# temp_controler_full.net
KiCad netlist of a schematic drawn in EAGLE
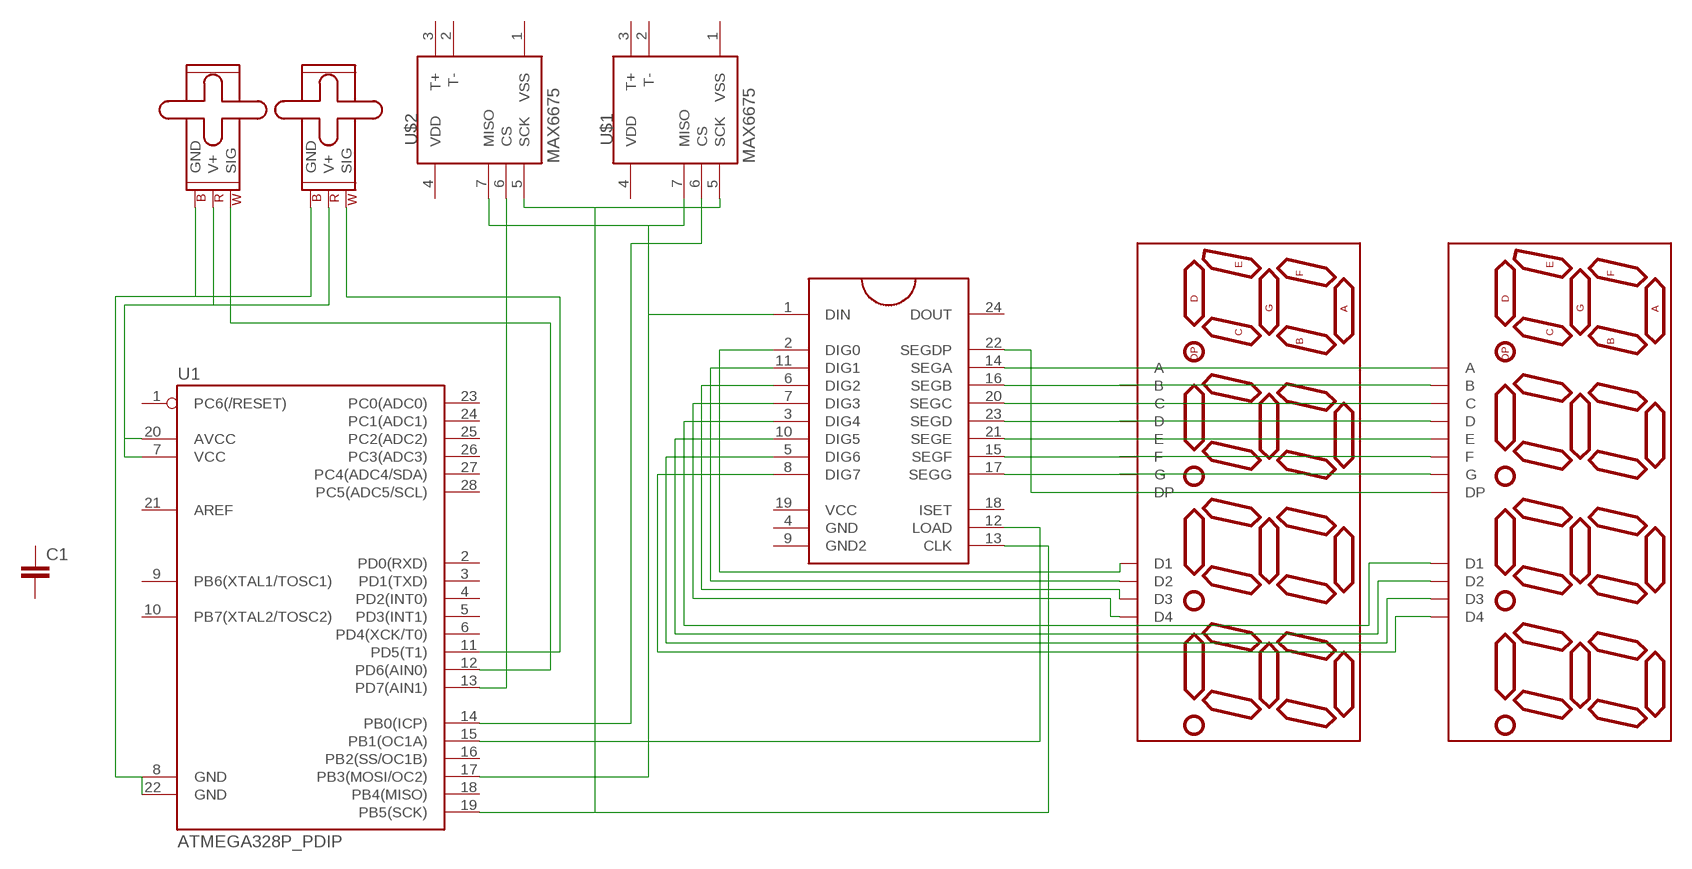
[diagram p0: schematic, sheet 1]

(export (version "E")
  (design (tool "Eeschema 10.0.6"))
  (components
    (comp (ref "C1")
      (value "0.1UF-50V-20%(PTH)KIT-EZ")
      (footprint "eagle-import:CAP-PTH-SMALL-KIT")
      (libsource (lib "eagle-import") (part "0.1UF-50V-20%(PTH)KIT-EZ"))
    )
    (comp (ref "M1")
      (value "SMALL_SERVO")
      (footprint "eagle-import:1X03")
      (libsource (lib "eagle-import") (part "SMALL_SERVO"))
    )
    (comp (ref "M2")
      (value "SMALL_SERVO")
      (footprint "eagle-import:1X03")
      (libsource (lib "eagle-import") (part "SMALL_SERVO"))
    )
    (comp (ref "U$1")
      (value "MAX6675")
      (footprint "eagle-import:SO08-MAX6675")
      (libsource (lib "eagle-import") (part "MAX6675"))
    )
    (comp (ref "U$2")
      (value "MAX6675")
      (footprint "eagle-import:SO08-MAX6675")
      (libsource (lib "eagle-import") (part "MAX6675"))
    )
    (comp (ref "U$3")
      (value "MAX7219DIP")
      (footprint "eagle-import:DIL24")
      (libsource (lib "eagle-import") (part "MAX7219DIP"))
    )
    (comp (ref "U$4")
      (value "7-SEGMENT-4DIGIT-COUNTERPTH")
      (footprint "eagle-import:7-SEGMENT-4DIGIT-COUNTER")
      (libsource (lib "eagle-import") (part "7-SEGMENT-4DIGIT-COUNTERPTH"))
    )
    (comp (ref "U$5")
      (value "7-SEGMENT-4DIGIT-COUNTERPTH")
      (footprint "eagle-import:7-SEGMENT-4DIGIT-COUNTER")
      (libsource (lib "eagle-import") (part "7-SEGMENT-4DIGIT-COUNTERPTH"))
    )
    (comp (ref "U1")
      (value "ATMEGA328P_PDIP")
      (footprint "eagle-import:DIL28-3")
      (libsource (lib "eagle-import") (part "ATMEGA328P_PDIP"))
    )
  )
  (nets
    (net (code "1") (name "Net-(M1-GND)") (class "Default")
      (node (ref "M1") (pin "3") (pinfunction "GND_3") (pintype "bidirectional"))
      (node (ref "M2") (pin "3") (pinfunction "GND_3") (pintype "bidirectional"))
      (node (ref "U1") (pin "22") (pinfunction "GND_22") (pintype "bidirectional"))
      (node (ref "U1") (pin "8") (pinfunction "GND_8") (pintype "bidirectional"))
    )
    (net (code "2") (name "Net-(M1-SIG)") (class "Default")
      (node (ref "M1") (pin "1") (pinfunction "SIG_1") (pintype "bidirectional"))
      (node (ref "U1") (pin "12") (pinfunction "PD6(AIN0)_12") (pintype "bidirectional"))
    )
    (net (code "3") (name "Net-(M1-V+)") (class "Default")
      (node (ref "M1") (pin "2") (pinfunction "V+_2") (pintype "bidirectional"))
      (node (ref "M2") (pin "2") (pinfunction "V+_2") (pintype "bidirectional"))
      (node (ref "U1") (pin "20") (pinfunction "AVCC_20") (pintype "bidirectional"))
      (node (ref "U1") (pin "7") (pinfunction "VCC_7") (pintype "bidirectional"))
    )
    (net (code "4") (name "Net-(M2-SIG)") (class "Default")
      (node (ref "M2") (pin "1") (pinfunction "SIG_1") (pintype "bidirectional"))
      (node (ref "U1") (pin "11") (pinfunction "PD5(T1)_11") (pintype "bidirectional"))
    )
    (net (code "5") (name "Net-(U$1-CS)") (class "Default")
      (node (ref "U$1") (pin "6") (pinfunction "CS_6") (pintype "bidirectional"))
      (node (ref "U1") (pin "14") (pinfunction "PB0(ICP)_14") (pintype "bidirectional"))
    )
    (net (code "6") (name "Net-(U$1-MISO)") (class "Default")
      (node (ref "U$1") (pin "7") (pinfunction "MISO_7") (pintype "bidirectional"))
      (node (ref "U$2") (pin "7") (pinfunction "MISO_7") (pintype "bidirectional"))
      (node (ref "U$3") (pin "1") (pinfunction "DIN_1") (pintype "bidirectional"))
      (node (ref "U1") (pin "17") (pinfunction "PB3(MOSI/OC2)_17") (pintype "bidirectional"))
    )
    (net (code "7") (name "Net-(U$1-SCK)") (class "Default")
      (node (ref "U$1") (pin "5") (pinfunction "SCK_5") (pintype "bidirectional"))
      (node (ref "U$2") (pin "5") (pinfunction "SCK_5") (pintype "bidirectional"))
      (node (ref "U$3") (pin "13") (pinfunction "CLK_13") (pintype "bidirectional"))
      (node (ref "U1") (pin "19") (pinfunction "PB5(SCK)_19") (pintype "bidirectional"))
    )
    (net (code "8") (name "Net-(U$2-CS)") (class "Default")
      (node (ref "U$2") (pin "6") (pinfunction "CS_6") (pintype "bidirectional"))
      (node (ref "U1") (pin "13") (pinfunction "PD7(AIN1)_13") (pintype "bidirectional"))
    )
    (net (code "9") (name "Net-(U$3-DIG0)") (class "Default")
      (node (ref "U$3") (pin "2") (pinfunction "DIG0_2") (pintype "bidirectional"))
      (node (ref "U$4") (pin "12") (pinfunction "D1_12") (pintype "bidirectional"))
    )
    (net (code "10") (name "Net-(U$3-DIG1)") (class "Default")
      (node (ref "U$3") (pin "11") (pinfunction "DIG1_11") (pintype "bidirectional"))
      (node (ref "U$4") (pin "9") (pinfunction "D2_9") (pintype "bidirectional"))
    )
    (net (code "11") (name "Net-(U$3-DIG2)") (class "Default")
      (node (ref "U$3") (pin "6") (pinfunction "DIG2_6") (pintype "bidirectional"))
      (node (ref "U$4") (pin "8") (pinfunction "D3_8") (pintype "bidirectional"))
    )
    (net (code "12") (name "Net-(U$3-DIG3)") (class "Default")
      (node (ref "U$3") (pin "7") (pinfunction "DIG3_7") (pintype "bidirectional"))
      (node (ref "U$4") (pin "6") (pinfunction "D4_6") (pintype "bidirectional"))
    )
    (net (code "13") (name "Net-(U$3-DIG4)") (class "Default")
      (node (ref "U$3") (pin "3") (pinfunction "DIG4_3") (pintype "bidirectional"))
      (node (ref "U$5") (pin "12") (pinfunction "D1_12") (pintype "bidirectional"))
    )
    (net (code "14") (name "Net-(U$3-DIG5)") (class "Default")
      (node (ref "U$3") (pin "10") (pinfunction "DIG5_10") (pintype "bidirectional"))
      (node (ref "U$5") (pin "9") (pinfunction "D2_9") (pintype "bidirectional"))
    )
    (net (code "15") (name "Net-(U$3-DIG6)") (class "Default")
      (node (ref "U$3") (pin "5") (pinfunction "DIG6_5") (pintype "bidirectional"))
      (node (ref "U$5") (pin "8") (pinfunction "D3_8") (pintype "bidirectional"))
    )
    (net (code "16") (name "Net-(U$3-DIG7)") (class "Default")
      (node (ref "U$3") (pin "8") (pinfunction "DIG7_8") (pintype "bidirectional"))
      (node (ref "U$5") (pin "6") (pinfunction "D4_6") (pintype "bidirectional"))
    )
    (net (code "17") (name "Net-(U$3-LOAD)") (class "Default")
      (node (ref "U$3") (pin "12") (pinfunction "LOAD_12") (pintype "bidirectional"))
      (node (ref "U1") (pin "15") (pinfunction "PB1(OC1A)_15") (pintype "bidirectional"))
    )
    (net (code "18") (name "Net-(U$3-SEGA)") (class "Default")
      (node (ref "U$3") (pin "14") (pinfunction "SEGA_14") (pintype "bidirectional"))
      (node (ref "U$4") (pin "11") (pinfunction "A_11") (pintype "bidirectional"))
      (node (ref "U$5") (pin "11") (pinfunction "A_11") (pintype "bidirectional"))
    )
    (net (code "19") (name "Net-(U$3-SEGB)") (class "Default")
      (node (ref "U$3") (pin "16") (pinfunction "SEGB_16") (pintype "bidirectional"))
      (node (ref "U$4") (pin "7") (pinfunction "B_7") (pintype "bidirectional"))
      (node (ref "U$5") (pin "7") (pinfunction "B_7") (pintype "bidirectional"))
    )
    (net (code "20") (name "Net-(U$3-SEGC)") (class "Default")
      (node (ref "U$3") (pin "20") (pinfunction "SEGC_20") (pintype "bidirectional"))
      (node (ref "U$4") (pin "4") (pinfunction "C_4") (pintype "bidirectional"))
      (node (ref "U$5") (pin "4") (pinfunction "C_4") (pintype "bidirectional"))
    )
    (net (code "21") (name "Net-(U$3-SEGD)") (class "Default")
      (node (ref "U$3") (pin "23") (pinfunction "SEGD_23") (pintype "bidirectional"))
      (node (ref "U$4") (pin "2") (pinfunction "D_2") (pintype "bidirectional"))
      (node (ref "U$5") (pin "2") (pinfunction "D_2") (pintype "bidirectional"))
    )
    (net (code "22") (name "Net-(U$3-SEGDP)") (class "Default")
      (node (ref "U$3") (pin "22") (pinfunction "SEGDP_22") (pintype "bidirectional"))
      (node (ref "U$4") (pin "3") (pinfunction "DP_3") (pintype "bidirectional"))
      (node (ref "U$5") (pin "3") (pinfunction "DP_3") (pintype "bidirectional"))
    )
    (net (code "23") (name "Net-(U$3-SEGE)") (class "Default")
      (node (ref "U$3") (pin "21") (pinfunction "SEGE_21") (pintype "bidirectional"))
      (node (ref "U$4") (pin "1") (pinfunction "E_1") (pintype "bidirectional"))
      (node (ref "U$5") (pin "1") (pinfunction "E_1") (pintype "bidirectional"))
    )
    (net (code "24") (name "Net-(U$3-SEGF)") (class "Default")
      (node (ref "U$3") (pin "15") (pinfunction "SEGF_15") (pintype "bidirectional"))
      (node (ref "U$4") (pin "10") (pinfunction "F_10") (pintype "bidirectional"))
      (node (ref "U$5") (pin "10") (pinfunction "F_10") (pintype "bidirectional"))
    )
    (net (code "25") (name "Net-(U$3-SEGG)") (class "Default")
      (node (ref "U$3") (pin "17") (pinfunction "SEGG_17") (pintype "bidirectional"))
      (node (ref "U$4") (pin "5") (pinfunction "G_5") (pintype "bidirectional"))
      (node (ref "U$5") (pin "5") (pinfunction "G_5") (pintype "bidirectional"))
    )
    (net (code "26") (name "unconnected-(C1-Pad1)") (class "Default")
      (node (ref "C1") (pin "1") (pinfunction "1_1") (pintype "passive"))
    )
    (net (code "27") (name "unconnected-(C1-Pad2)") (class "Default")
      (node (ref "C1") (pin "2") (pinfunction "2_2") (pintype "passive"))
    )
    (net (code "28") (name "unconnected-(U$1-T+-Pad3)") (class "Default")
      (node (ref "U$1") (pin "3") (pinfunction "T+_3") (pintype "bidirectional"))
    )
    (net (code "29") (name "unconnected-(U$1-T--Pad2)") (class "Default")
      (node (ref "U$1") (pin "2") (pinfunction "T-_2") (pintype "bidirectional"))
    )
    (net (code "30") (name "unconnected-(U$1-VDD-Pad4)") (class "Default")
      (node (ref "U$1") (pin "4") (pinfunction "VDD_4") (pintype "bidirectional"))
    )
    (net (code "31") (name "unconnected-(U$1-VSS-Pad1)") (class "Default")
      (node (ref "U$1") (pin "1") (pinfunction "VSS_1") (pintype "bidirectional"))
    )
    (net (code "32") (name "unconnected-(U$2-T+-Pad3)") (class "Default")
      (node (ref "U$2") (pin "3") (pinfunction "T+_3") (pintype "bidirectional"))
    )
    (net (code "33") (name "unconnected-(U$2-T--Pad2)") (class "Default")
      (node (ref "U$2") (pin "2") (pinfunction "T-_2") (pintype "bidirectional"))
    )
    (net (code "34") (name "unconnected-(U$2-VDD-Pad4)") (class "Default")
      (node (ref "U$2") (pin "4") (pinfunction "VDD_4") (pintype "bidirectional"))
    )
    (net (code "35") (name "unconnected-(U$2-VSS-Pad1)") (class "Default")
      (node (ref "U$2") (pin "1") (pinfunction "VSS_1") (pintype "bidirectional"))
    )
    (net (code "36") (name "unconnected-(U$3-DOUT-Pad24)") (class "Default")
      (node (ref "U$3") (pin "24") (pinfunction "DOUT_24") (pintype "bidirectional"))
    )
    (net (code "37") (name "unconnected-(U$3-GND-Pad4)") (class "Default")
      (node (ref "U$3") (pin "4") (pinfunction "GND_4") (pintype "bidirectional"))
    )
    (net (code "38") (name "unconnected-(U$3-GND2-Pad9)") (class "Default")
      (node (ref "U$3") (pin "9") (pinfunction "GND2_9") (pintype "bidirectional"))
    )
    (net (code "39") (name "unconnected-(U$3-ISET-Pad18)") (class "Default")
      (node (ref "U$3") (pin "18") (pinfunction "ISET_18") (pintype "bidirectional"))
    )
    (net (code "40") (name "unconnected-(U$3-VCC-Pad19)") (class "Default")
      (node (ref "U$3") (pin "19") (pinfunction "VCC_19") (pintype "bidirectional"))
    )
    (net (code "41") (name "unconnected-(U1-AREF-Pad21)") (class "Default")
      (node (ref "U1") (pin "21") (pinfunction "AREF_21") (pintype "bidirectional"))
    )
    (net (code "42") (name "unconnected-(U1-PB2(SS{slash}OC1B)-Pad16)") (class "Default")
      (node (ref "U1") (pin "16") (pinfunction "PB2(SS/OC1B)_16") (pintype "bidirectional"))
    )
    (net (code "43") (name "unconnected-(U1-PB4(MISO)-Pad18)") (class "Default")
      (node (ref "U1") (pin "18") (pinfunction "PB4(MISO)_18") (pintype "bidirectional"))
    )
    (net (code "44") (name "unconnected-(U1-PB6(XTAL1{slash}TOSC1)-Pad9)") (class "Default")
      (node (ref "U1") (pin "9") (pinfunction "PB6(XTAL1/TOSC1)_9") (pintype "bidirectional"))
    )
    (net (code "45") (name "unconnected-(U1-PB7(XTAL2{slash}TOSC2)-Pad10)") (class "Default")
      (node (ref "U1") (pin "10") (pinfunction "PB7(XTAL2/TOSC2)_10") (pintype "bidirectional"))
    )
    (net (code "46") (name "unconnected-(U1-PC0(ADC0)-Pad23)") (class "Default")
      (node (ref "U1") (pin "23") (pinfunction "PC0(ADC0)_23") (pintype "bidirectional"))
    )
    (net (code "47") (name "unconnected-(U1-PC1(ADC1)-Pad24)") (class "Default")
      (node (ref "U1") (pin "24") (pinfunction "PC1(ADC1)_24") (pintype "bidirectional"))
    )
    (net (code "48") (name "unconnected-(U1-PC2(ADC2)-Pad25)") (class "Default")
      (node (ref "U1") (pin "25") (pinfunction "PC2(ADC2)_25") (pintype "bidirectional"))
    )
    (net (code "49") (name "unconnected-(U1-PC3(ADC3)-Pad26)") (class "Default")
      (node (ref "U1") (pin "26") (pinfunction "PC3(ADC3)_26") (pintype "bidirectional"))
    )
    (net (code "50") (name "unconnected-(U1-PC4(ADC4{slash}SDA)-Pad27)") (class "Default")
      (node (ref "U1") (pin "27") (pinfunction "PC4(ADC4/SDA)_27") (pintype "bidirectional"))
    )
    (net (code "51") (name "unconnected-(U1-PC5(ADC5{slash}SCL)-Pad28)") (class "Default")
      (node (ref "U1") (pin "28") (pinfunction "PC5(ADC5/SCL)_28") (pintype "bidirectional"))
    )
    (net (code "52") (name "unconnected-(U1-PC6({slash}RESET)-Pad1)") (class "Default")
      (node (ref "U1") (pin "1") (pinfunction "PC6(/RESET)_1") (pintype "bidirectional"))
    )
    (net (code "53") (name "unconnected-(U1-PD0(RXD)-Pad2)") (class "Default")
      (node (ref "U1") (pin "2") (pinfunction "PD0(RXD)_2") (pintype "bidirectional"))
    )
    (net (code "54") (name "unconnected-(U1-PD1(TXD)-Pad3)") (class "Default")
      (node (ref "U1") (pin "3") (pinfunction "PD1(TXD)_3") (pintype "bidirectional"))
    )
    (net (code "55") (name "unconnected-(U1-PD2(INT0)-Pad4)") (class "Default")
      (node (ref "U1") (pin "4") (pinfunction "PD2(INT0)_4") (pintype "bidirectional"))
    )
    (net (code "56") (name "unconnected-(U1-PD3(INT1)-Pad5)") (class "Default")
      (node (ref "U1") (pin "5") (pinfunction "PD3(INT1)_5") (pintype "bidirectional"))
    )
    (net (code "57") (name "unconnected-(U1-PD4(XCK{slash}T0)-Pad6)") (class "Default")
      (node (ref "U1") (pin "6") (pinfunction "PD4(XCK/T0)_6") (pintype "bidirectional"))
    )
  )
)
